# Fuente_Alimentacion.net
KiCad netlist of a schematic drawn in Altium Designer
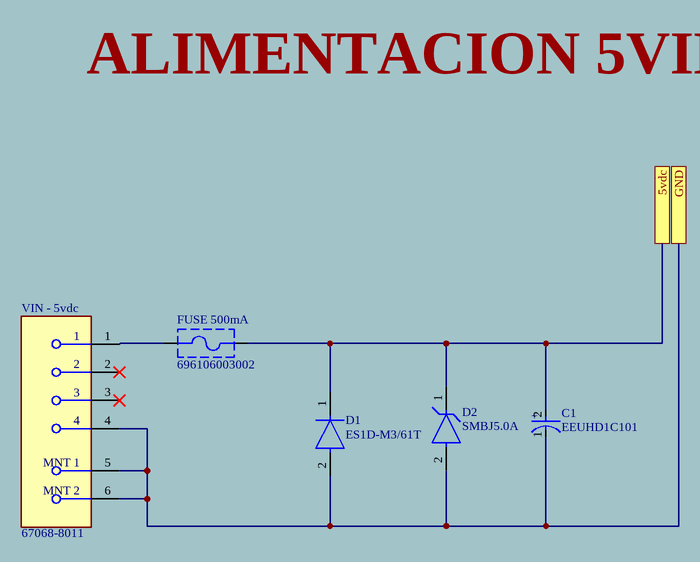
[diagram p0: Fuente Alimentacion.SchDoc]

(export (version "E")
  (design (tool "Eeschema 10.0.6"))
  (components
    (comp (ref "C1")
      (value "EEUHD1C101")
      (footprint "FP-RAD-TH-D_5_0_5-L_11_1-MFG")
      (description "Aluminum Electrolytic Capacitors (Radial Lead Type) AEC-Q200 Qualified 100uF ±20% 16V")
      (fields (field (name "TOLERANCE") "20%") (field (name "VOLTAGE") "16V"))
      (libsource (lib "Altium Content Vault") (part "a00bbbee19879c290e62620ae7e47b1"))
    )
    (comp (ref "D1")
      (value "ES1D-M3/61T")
      (footprint "FP-SMA-MFG")
      (description "DIODE GEN PURP 200V 1A DO214AC")
      (libsource (lib "Altium Content Vault") (part "d7152d700b627762746794eb795d46e"))
    )
    (comp (ref "D2")
      (value "SMBJ5.0A")
      (footprint "FP-SMBJ-MFG")
      (description "TVS DIODE 5V 9.2V DO214AA")
      (fields
        (field (name "OCTOPART") "https://octopart.com/smbj5.0a-littelfuse-8835")
        (field (name "MANUFACTURER") "Littelfuse Inc")
      )
      (libsource (lib "Altium Content Vault") (part "f813f71cba58e380607f5dd3caf9714"))
    )
    (comp (ref "FUSE 500mA")
      (value "696106003002")
      (footprint "696106003002")
      (libsource (lib "Altium Content Vault") (part "Fuse Holder"))
    )
    (comp (ref "VIN - 5vdc")
      (value "67068-8011")
      (footprint "FP-67068-8011-MFG")
      (description "67068-8011 Conn USB 2.0 Type B RCP 4 POS 2.5mm Solder RA Thru-Hole 4 Terminal 1 Port USB 2.0 Tray")
      (libsource (lib "Altium Content Vault") (part "79e6714efa0bb2f851c24b2688127c9"))
    )
  )
  (nets
    (net (code "1") (name "/5vdc") (class "Default")
      (node (ref "C1") (pin "2") (pinfunction "A_2") (pintype "passive"))
      (node (ref "D1") (pin "1") (pinfunction "C_1") (pintype "passive"))
      (node (ref "D2") (pin "1") (pinfunction "C_1") (pintype "passive"))
      (node (ref "FUSE 500mA") (pin "1") (pinfunction "1_1") (pintype "passive"))
    )
    (net (code "2") (name "/GND") (class "Default")
      (node (ref "C1") (pin "1") (pinfunction "C_1") (pintype "passive"))
      (node (ref "D1") (pin "2") (pinfunction "A_2") (pintype "passive"))
      (node (ref "D2") (pin "2") (pinfunction "A_2") (pintype "passive"))
      (node (ref "VIN - 5vdc") (pin "4") (pinfunction "4_4") (pintype "passive"))
      (node (ref "VIN - 5vdc") (pin "5") (pinfunction "MNT_1_5") (pintype "passive"))
      (node (ref "VIN - 5vdc") (pin "6") (pinfunction "MNT_2_6") (pintype "passive"))
    )
    (net (code "3") (name "Net-(FUSE 500mA-Pad2)") (class "Default")
      (node (ref "FUSE 500mA") (pin "2") (pinfunction "2_2") (pintype "passive"))
      (node (ref "VIN - 5vdc") (pin "1") (pinfunction "1_1") (pintype "passive"))
    )
    (net (code "4") (name "unconnected-(VIN - 5vdc-Pad2)") (class "Default")
      (node (ref "VIN - 5vdc") (pin "2") (pinfunction "2_2") (pintype "passive+no_connect"))
    )
    (net (code "5") (name "unconnected-(VIN - 5vdc-Pad3)") (class "Default")
      (node (ref "VIN - 5vdc") (pin "3") (pinfunction "3_3") (pintype "passive+no_connect"))
    )
  )
)
